# design.net
KiCad netlist of a schematic drawn in Altium Designer
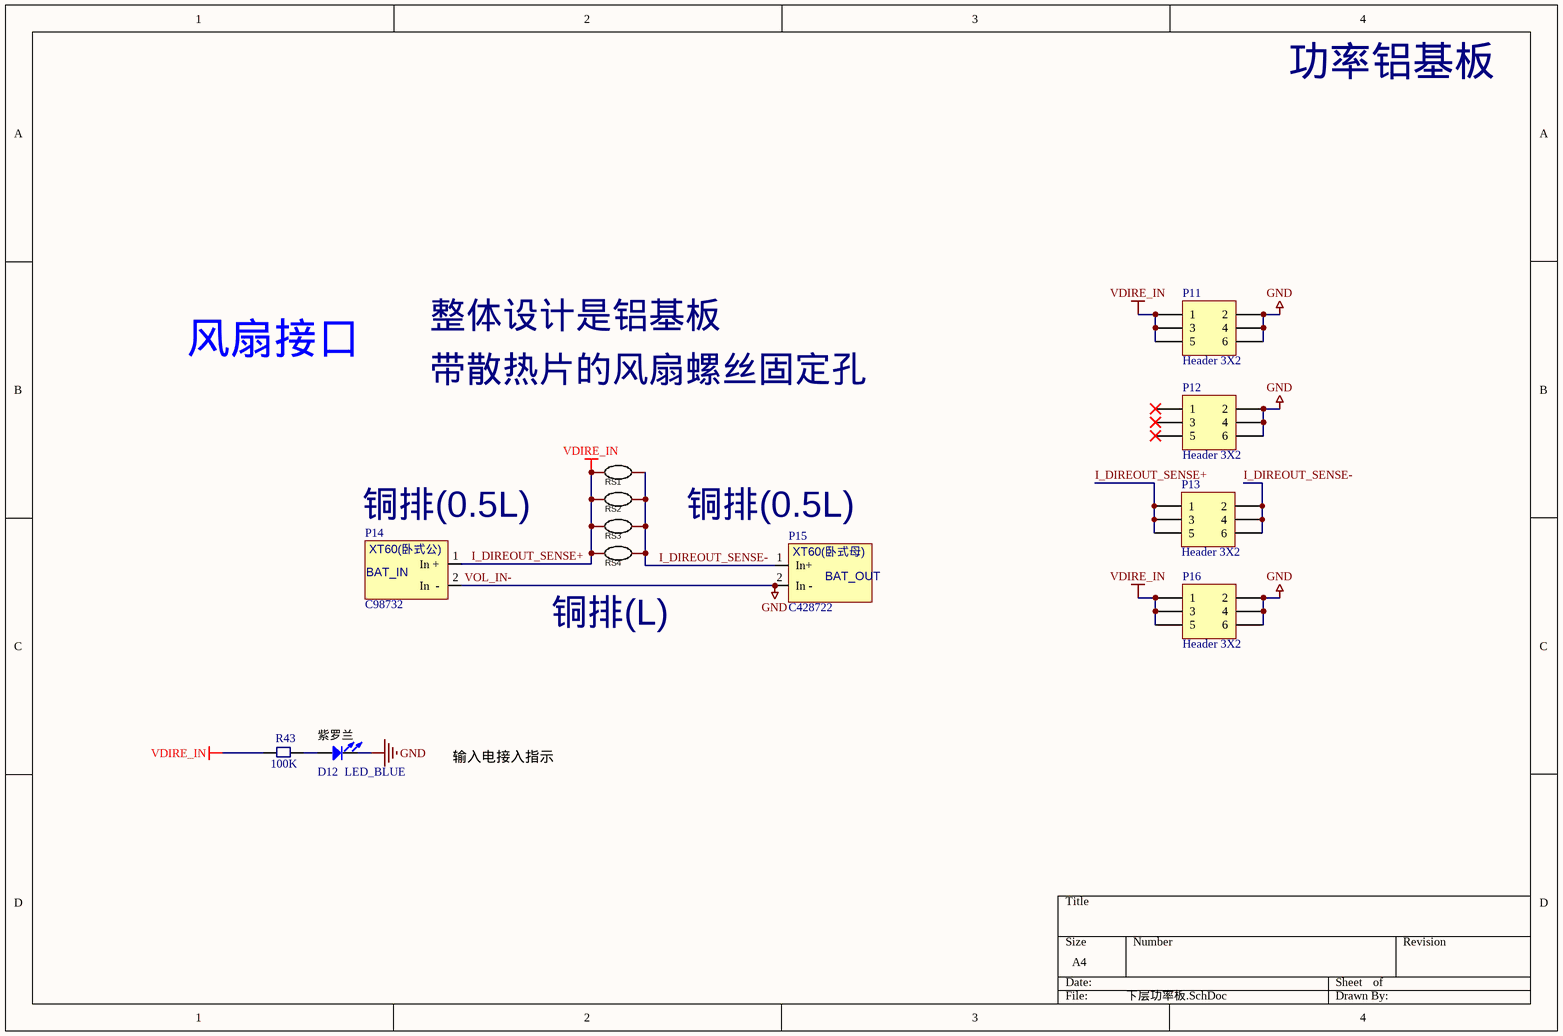
[diagram p0: 下层功率板.SchDoc]

(export (version "E")
  (design (tool "Eeschema 10.0.6"))
  (components
    (comp (ref "D12")
      (value "LED_BLUE")
      (footprint "LED-0603W")
      (description "Typical INFRARED GaAs LED")
      (fields (field (name "PUBLISHER") "Altium Limited"))
      (libsource (lib "超级电容") (part "LED"))
    )
    (comp (ref "P11")
      (value "Header 3X2")
      (footprint "HDR-SMD_6P-P2.54-V-M-R2-C3-LS7.5-2")
      (description "Header, 3-Pin, Dual row\r\nPZ127-2-03-S\r\nC3975186")
      (fields (field (name "PUBLISHER") "Altium Limited"))
      (libsource (lib "Miscellaneous Connectors") (part "Header 3X2"))
    )
    (comp (ref "P12")
      (value "Header 3X2")
      (footprint "HDR-SMD_6P-P2.54-V-M-R2-C3-LS7.5-2")
      (description "Header, 3-Pin, Dual row\r\nPZ127-2-03-S\r\nC3975186")
      (fields (field (name "PUBLISHER") "Altium Limited"))
      (libsource (lib "Miscellaneous Connectors") (part "Header 3X2"))
    )
    (comp (ref "P13")
      (value "Header 3X2")
      (footprint "HDR-SMD_6P-P2.54-V-M-R2-C3-LS7.5-2")
      (description "Header, 3-Pin, Dual row\r\nPZ127-2-03-S\r\nC3975186")
      (fields (field (name "PUBLISHER") "Altium Limited"))
      (libsource (lib "Miscellaneous Connectors") (part "Header 3X2"))
    )
    (comp (ref "P14")
      (value "C98732")
      (footprint "XT60 PT M")
      (description "XT60_PW_M\r\nXT60公头输入")
      (libsource (lib "Titan_Schlib1") (part "P_PW_XT60_M_卧式"))
    )
    (comp (ref "P15")
      (value "C428722")
      (footprint "XT60 PT F")
      (description "XT60_PW_M\r\nXT60母头输入")
      (libsource (lib "Titan_Schlib1") (part "P_PW_XT60_FM_卧式"))
    )
    (comp (ref "P16")
      (value "Header 3X2")
      (footprint "HDR-SMD_6P-P2.54-V-M-R2-C3-LS7.5-2")
      (description "Header, 3-Pin, Dual row\r\nPZ127-2-03-S\r\nC3975186")
      (fields (field (name "PUBLISHER") "Altium Limited"))
      (libsource (lib "Miscellaneous Connectors") (part "Header 3X2"))
    )
    (comp (ref "R43")
      (value "100K")
      (footprint "R0805")
      (description "Resistor")
      (fields (field (name "PUBLISHER") "Altium Limited"))
      (libsource (lib "超级电容") (part "Res"))
    )
    (comp (ref "RS1")
      (value "HolRS3920-5W-0.3mR-1%")
      (footprint "R3920")
      (fields (field (name "MANUFACTURER") "Milliohm(毫欧)") (field (name "TOLERANCE") "±1%"))
      (libsource (lib "SchLib") (part "C558626"))
    )
    (comp (ref "RS2")
      (value "HolRS3920-5W-0.3mR-1%")
      (footprint "R3920")
      (fields (field (name "MANUFACTURER") "Milliohm(毫欧)") (field (name "TOLERANCE") "±1%"))
      (libsource (lib "SchLib") (part "C558626"))
    )
    (comp (ref "RS3")
      (value "HolRS3920-5W-0.3mR-1%")
      (footprint "R3920")
      (fields (field (name "MANUFACTURER") "Milliohm(毫欧)") (field (name "TOLERANCE") "±1%"))
      (libsource (lib "SchLib") (part "C558626"))
    )
    (comp (ref "RS4")
      (value "HolRS3920-5W-0.3mR-1%")
      (footprint "R3920")
      (fields (field (name "MANUFACTURER") "Milliohm(毫欧)") (field (name "TOLERANCE") "±1%"))
      (libsource (lib "SchLib") (part "C558626"))
    )
  )
  (nets
    (net (code "1") (name "/I_DIREOUT_SENSE-") (class "Default")
      (node (ref "P13") (pin "2") (pinfunction "2_2") (pintype "passive"))
      (node (ref "P13") (pin "4") (pinfunction "4_4") (pintype "passive"))
      (node (ref "P13") (pin "6") (pinfunction "6_6") (pintype "passive"))
      (node (ref "P15") (pin "1") (pinfunction "In+_1") (pintype "passive"))
      (node (ref "RS1") (pin "2") (pinfunction "2_2") (pintype "passive"))
      (node (ref "RS2") (pin "2") (pinfunction "2_2") (pintype "passive"))
      (node (ref "RS3") (pin "2") (pinfunction "2_2") (pintype "passive"))
      (node (ref "RS4") (pin "2") (pinfunction "2_2") (pintype "passive"))
    )
    (net (code "2") (name "GND") (class "Default")
      (node (ref "D12") (pin "2") (pinfunction "K_2") (pintype "passive"))
      (node (ref "P11") (pin "2") (pinfunction "2_2") (pintype "passive"))
      (node (ref "P11") (pin "4") (pinfunction "4_4") (pintype "passive"))
      (node (ref "P11") (pin "6") (pinfunction "6_6") (pintype "passive"))
      (node (ref "P12") (pin "2") (pinfunction "2_2") (pintype "passive"))
      (node (ref "P12") (pin "4") (pinfunction "4_4") (pintype "passive"))
      (node (ref "P12") (pin "6") (pinfunction "6_6") (pintype "passive"))
      (node (ref "P14") (pin "2") (pinfunction "In__-_2") (pintype "passive"))
      (node (ref "P15") (pin "2") (pinfunction "In_-_2") (pintype "passive"))
      (node (ref "P16") (pin "2") (pinfunction "2_2") (pintype "passive"))
      (node (ref "P16") (pin "4") (pinfunction "4_4") (pintype "passive"))
      (node (ref "P16") (pin "6") (pinfunction "6_6") (pintype "passive"))
    )
    (net (code "3") (name "Net-(D12-A)") (class "Default")
      (node (ref "D12") (pin "1") (pinfunction "A_1") (pintype "passive"))
      (node (ref "R43") (pin "1") (pinfunction "1_1") (pintype "passive"))
    )
    (net (code "4") (name "VDIRE_IN") (class "Default")
      (node (ref "P11") (pin "1") (pinfunction "1_1") (pintype "passive"))
      (node (ref "P11") (pin "3") (pinfunction "3_3") (pintype "passive"))
      (node (ref "P11") (pin "5") (pinfunction "5_5") (pintype "passive"))
      (node (ref "P13") (pin "1") (pinfunction "1_1") (pintype "passive"))
      (node (ref "P13") (pin "3") (pinfunction "3_3") (pintype "passive"))
      (node (ref "P13") (pin "5") (pinfunction "5_5") (pintype "passive"))
      (node (ref "P14") (pin "1") (pinfunction "In_+_1") (pintype "passive"))
      (node (ref "P16") (pin "1") (pinfunction "1_1") (pintype "passive"))
      (node (ref "P16") (pin "3") (pinfunction "3_3") (pintype "passive"))
      (node (ref "P16") (pin "5") (pinfunction "5_5") (pintype "passive"))
      (node (ref "R43") (pin "2") (pinfunction "2_2") (pintype "passive"))
      (node (ref "RS1") (pin "1") (pinfunction "1_1") (pintype "passive"))
      (node (ref "RS2") (pin "1") (pinfunction "1_1") (pintype "passive"))
      (node (ref "RS3") (pin "1") (pinfunction "1_1") (pintype "passive"))
      (node (ref "RS4") (pin "1") (pinfunction "1_1") (pintype "passive"))
    )
    (net (code "5") (name "unconnected-(P12-Pad1)") (class "Default")
      (node (ref "P12") (pin "1") (pinfunction "1_1") (pintype "passive+no_connect"))
    )
    (net (code "6") (name "unconnected-(P12-Pad3)") (class "Default")
      (node (ref "P12") (pin "3") (pinfunction "3_3") (pintype "passive+no_connect"))
    )
    (net (code "7") (name "unconnected-(P12-Pad5)") (class "Default")
      (node (ref "P12") (pin "5") (pinfunction "5_5") (pintype "passive+no_connect"))
    )
  )
)
